# vco_pots.net
KiCad netlist of a schematic drawn in EAGLE
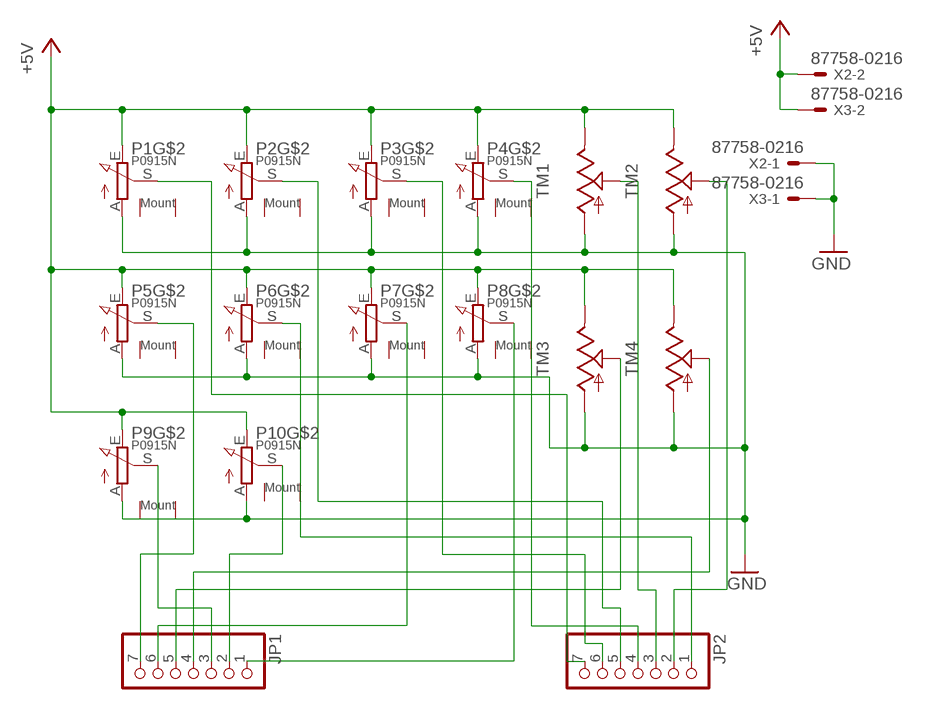
[diagram p0: schematic, sheet 1]

(export (version "E")
  (design (tool "Eeschema 10.0.6"))
  (components
    (comp (ref "JP1")
      (value "PINHD-1X7")
      (footprint "eagle-import:1X07")
      (libsource (lib "eagle-import") (part "PINHD-1X7"))
    )
    (comp (ref "JP2")
      (value "PINHD-1X7")
      (footprint "eagle-import:1X07")
      (libsource (lib "eagle-import") (part "PINHD-1X7"))
    )
    (comp (ref "P1")
      (value "P0915N")
      (footprint "eagle-import:P0915N")
      (libsource (lib "eagle-import") (part "P0915N"))
    )
    (comp (ref "P2")
      (value "P0915N")
      (footprint "eagle-import:P0915N")
      (libsource (lib "eagle-import") (part "P0915N"))
    )
    (comp (ref "P3")
      (value "P0915N")
      (footprint "eagle-import:P0915N")
      (libsource (lib "eagle-import") (part "P0915N"))
    )
    (comp (ref "P4")
      (value "P0915N")
      (footprint "eagle-import:P0915N")
      (libsource (lib "eagle-import") (part "P0915N"))
    )
    (comp (ref "P5")
      (value "P0915N")
      (footprint "eagle-import:P0915N")
      (libsource (lib "eagle-import") (part "P0915N"))
    )
    (comp (ref "P6")
      (value "P0915N")
      (footprint "eagle-import:P0915N")
      (libsource (lib "eagle-import") (part "P0915N"))
    )
    (comp (ref "P7")
      (value "P0915N")
      (footprint "eagle-import:P0915N")
      (libsource (lib "eagle-import") (part "P0915N"))
    )
    (comp (ref "P8")
      (value "P0915N")
      (footprint "eagle-import:P0915N")
      (libsource (lib "eagle-import") (part "P0915N"))
    )
    (comp (ref "P9")
      (value "P0915N")
      (footprint "eagle-import:P0915N")
      (libsource (lib "eagle-import") (part "P0915N"))
    )
    (comp (ref "P10")
      (value "P0915N")
      (footprint "eagle-import:P0915N")
      (libsource (lib "eagle-import") (part "P0915N"))
    )
    (comp (ref "TM1")
      (value "TRIMSLIDE60")
      (footprint "eagle-import:SLIDEPOT-60")
      (libsource (lib "eagle-import") (part "TRIMSLIDE60"))
    )
    (comp (ref "TM2")
      (value "TRIMSLIDE60")
      (footprint "eagle-import:SLIDEPOT-60")
      (libsource (lib "eagle-import") (part "TRIMSLIDE60"))
    )
    (comp (ref "TM3")
      (value "TRIMSLIDE60")
      (footprint "eagle-import:SLIDEPOT-60")
      (libsource (lib "eagle-import") (part "TRIMSLIDE60"))
    )
    (comp (ref "TM4")
      (value "TRIMSLIDE60")
      (footprint "eagle-import:SLIDEPOT-60")
      (libsource (lib "eagle-import") (part "TRIMSLIDE60"))
    )
    (comp (ref "X2")
      (value "87758-0216")
      (footprint "eagle-import:87758-0216")
      (libsource (lib "eagle-import") (part "87758-0216"))
    )
    (comp (ref "X3")
      (value "87758-0216")
      (footprint "eagle-import:87758-0216")
      (libsource (lib "eagle-import") (part "87758-0216"))
    )
  )
  (nets
    (net (code "1") (name "+5V") (class "Default")
      (node (ref "P1") (pin "E") (pinfunction "E_E") (pintype "passive"))
      (node (ref "P10") (pin "E") (pinfunction "E_E") (pintype "passive"))
      (node (ref "P2") (pin "E") (pinfunction "E_E") (pintype "passive"))
      (node (ref "P3") (pin "E") (pinfunction "E_E") (pintype "passive"))
      (node (ref "P4") (pin "E") (pinfunction "E_E") (pintype "passive"))
      (node (ref "P5") (pin "E") (pinfunction "E_E") (pintype "passive"))
      (node (ref "P6") (pin "E") (pinfunction "E_E") (pintype "passive"))
      (node (ref "P7") (pin "E") (pinfunction "E_E") (pintype "passive"))
      (node (ref "P8") (pin "E") (pinfunction "E_E") (pintype "passive"))
      (node (ref "P9") (pin "E") (pinfunction "E_E") (pintype "passive"))
      (node (ref "TM1") (pin "B") (pinfunction "B_B") (pintype "passive"))
      (node (ref "TM2") (pin "B") (pinfunction "B_B") (pintype "passive"))
      (node (ref "TM3") (pin "B") (pinfunction "B_B") (pintype "passive"))
      (node (ref "TM4") (pin "B") (pinfunction "B_B") (pintype "passive"))
      (node (ref "X2") (pin "2") (pinfunction "S_2") (pintype "passive"))
      (node (ref "X3") (pin "2") (pinfunction "S_2") (pintype "passive"))
    )
    (net (code "2") (name "GND") (class "Default")
      (node (ref "P1") (pin "A") (pinfunction "A_A") (pintype "passive"))
      (node (ref "P10") (pin "A") (pinfunction "A_A") (pintype "passive"))
      (node (ref "P2") (pin "A") (pinfunction "A_A") (pintype "passive"))
      (node (ref "P3") (pin "A") (pinfunction "A_A") (pintype "passive"))
      (node (ref "P4") (pin "A") (pinfunction "A_A") (pintype "passive"))
      (node (ref "P5") (pin "A") (pinfunction "A_A") (pintype "passive"))
      (node (ref "P6") (pin "A") (pinfunction "A_A") (pintype "passive"))
      (node (ref "P7") (pin "A") (pinfunction "A_A") (pintype "passive"))
      (node (ref "P8") (pin "A") (pinfunction "A_A") (pintype "passive"))
      (node (ref "P9") (pin "A") (pinfunction "A_A") (pintype "passive"))
      (node (ref "TM1") (pin "A") (pinfunction "A_A") (pintype "passive"))
      (node (ref "TM2") (pin "A") (pinfunction "A_A") (pintype "passive"))
      (node (ref "TM3") (pin "A") (pinfunction "A_A") (pintype "passive"))
      (node (ref "TM4") (pin "A") (pinfunction "A_A") (pintype "passive"))
      (node (ref "X2") (pin "1") (pinfunction "S_1") (pintype "passive"))
      (node (ref "X3") (pin "1") (pinfunction "S_1") (pintype "passive"))
    )
    (net (code "3") (name "Net-(JP1-Pad1)") (class "Default")
      (node (ref "JP1") (pin "1") (pinfunction "1_1") (pintype "passive"))
      (node (ref "P8") (pin "S") (pinfunction "S_S") (pintype "passive"))
    )
    (net (code "4") (name "Net-(JP1-Pad2)") (class "Default")
      (node (ref "JP1") (pin "2") (pinfunction "2_2") (pintype "passive"))
      (node (ref "P10") (pin "S") (pinfunction "S_S") (pintype "passive"))
    )
    (net (code "5") (name "Net-(JP1-Pad3)") (class "Default")
      (node (ref "JP1") (pin "3") (pinfunction "3_3") (pintype "passive"))
      (node (ref "P9") (pin "S") (pinfunction "S_S") (pintype "passive"))
    )
    (net (code "6") (name "Net-(JP1-Pad4)") (class "Default")
      (node (ref "JP1") (pin "4") (pinfunction "4_4") (pintype "passive"))
      (node (ref "TM4") (pin "WIPER") (pinfunction "WIPER_WIPER") (pintype "passive"))
    )
    (net (code "7") (name "Net-(JP1-Pad5)") (class "Default")
      (node (ref "JP1") (pin "5") (pinfunction "5_5") (pintype "passive"))
      (node (ref "TM3") (pin "WIPER") (pinfunction "WIPER_WIPER") (pintype "passive"))
    )
    (net (code "8") (name "Net-(JP1-Pad6)") (class "Default")
      (node (ref "JP1") (pin "6") (pinfunction "6_6") (pintype "passive"))
      (node (ref "P7") (pin "S") (pinfunction "S_S") (pintype "passive"))
    )
    (net (code "9") (name "Net-(JP1-Pad7)") (class "Default")
      (node (ref "JP1") (pin "7") (pinfunction "7_7") (pintype "passive"))
      (node (ref "P5") (pin "S") (pinfunction "S_S") (pintype "passive"))
    )
    (net (code "10") (name "Net-(JP2-Pad1)") (class "Default")
      (node (ref "JP2") (pin "1") (pinfunction "1_1") (pintype "passive"))
      (node (ref "P6") (pin "S") (pinfunction "S_S") (pintype "passive"))
    )
    (net (code "11") (name "Net-(JP2-Pad2)") (class "Default")
      (node (ref "JP2") (pin "2") (pinfunction "2_2") (pintype "passive"))
      (node (ref "TM2") (pin "WIPER") (pinfunction "WIPER_WIPER") (pintype "passive"))
    )
    (net (code "12") (name "Net-(JP2-Pad3)") (class "Default")
      (node (ref "JP2") (pin "3") (pinfunction "3_3") (pintype "passive"))
      (node (ref "TM1") (pin "WIPER") (pinfunction "WIPER_WIPER") (pintype "passive"))
    )
    (net (code "13") (name "Net-(JP2-Pad4)") (class "Default")
      (node (ref "JP2") (pin "4") (pinfunction "4_4") (pintype "passive"))
      (node (ref "P4") (pin "S") (pinfunction "S_S") (pintype "passive"))
    )
    (net (code "14") (name "Net-(JP2-Pad5)") (class "Default")
      (node (ref "JP2") (pin "5") (pinfunction "5_5") (pintype "passive"))
      (node (ref "P2") (pin "S") (pinfunction "S_S") (pintype "passive"))
    )
    (net (code "15") (name "Net-(JP2-Pad6)") (class "Default")
      (node (ref "JP2") (pin "6") (pinfunction "6_6") (pintype "passive"))
      (node (ref "P3") (pin "S") (pinfunction "S_S") (pintype "passive"))
    )
    (net (code "16") (name "Net-(JP2-Pad7)") (class "Default")
      (node (ref "JP2") (pin "7") (pinfunction "7_7") (pintype "passive"))
      (node (ref "P1") (pin "S") (pinfunction "S_S") (pintype "passive"))
    )
    (net (code "17") (name "unconnected-(P1A-GND-PadGND@1)") (class "Default")
      (node (ref "P1") (pin "GND@1") (pinfunction "GND_GND@1") (pintype "passive"))
    )
    (net (code "18") (name "unconnected-(P1A-GND-PadGND@2)") (class "Default")
      (node (ref "P1") (pin "GND@2") (pinfunction "GND_GND@2") (pintype "passive"))
    )
    (net (code "19") (name "unconnected-(P2A-GND-PadGND@1)") (class "Default")
      (node (ref "P2") (pin "GND@1") (pinfunction "GND_GND@1") (pintype "passive"))
    )
    (net (code "20") (name "unconnected-(P2A-GND-PadGND@2)") (class "Default")
      (node (ref "P2") (pin "GND@2") (pinfunction "GND_GND@2") (pintype "passive"))
    )
    (net (code "21") (name "unconnected-(P3A-GND-PadGND@1)") (class "Default")
      (node (ref "P3") (pin "GND@1") (pinfunction "GND_GND@1") (pintype "passive"))
    )
    (net (code "22") (name "unconnected-(P3A-GND-PadGND@2)") (class "Default")
      (node (ref "P3") (pin "GND@2") (pinfunction "GND_GND@2") (pintype "passive"))
    )
    (net (code "23") (name "unconnected-(P4A-GND-PadGND@1)") (class "Default")
      (node (ref "P4") (pin "GND@1") (pinfunction "GND_GND@1") (pintype "passive"))
    )
    (net (code "24") (name "unconnected-(P4A-GND-PadGND@2)") (class "Default")
      (node (ref "P4") (pin "GND@2") (pinfunction "GND_GND@2") (pintype "passive"))
    )
    (net (code "25") (name "unconnected-(P5A-GND-PadGND@1)") (class "Default")
      (node (ref "P5") (pin "GND@1") (pinfunction "GND_GND@1") (pintype "passive"))
    )
    (net (code "26") (name "unconnected-(P5A-GND-PadGND@2)") (class "Default")
      (node (ref "P5") (pin "GND@2") (pinfunction "GND_GND@2") (pintype "passive"))
    )
    (net (code "27") (name "unconnected-(P6A-GND-PadGND@1)") (class "Default")
      (node (ref "P6") (pin "GND@1") (pinfunction "GND_GND@1") (pintype "passive"))
    )
    (net (code "28") (name "unconnected-(P6A-GND-PadGND@2)") (class "Default")
      (node (ref "P6") (pin "GND@2") (pinfunction "GND_GND@2") (pintype "passive"))
    )
    (net (code "29") (name "unconnected-(P7A-GND-PadGND@1)") (class "Default")
      (node (ref "P7") (pin "GND@1") (pinfunction "GND_GND@1") (pintype "passive"))
    )
    (net (code "30") (name "unconnected-(P7A-GND-PadGND@2)") (class "Default")
      (node (ref "P7") (pin "GND@2") (pinfunction "GND_GND@2") (pintype "passive"))
    )
    (net (code "31") (name "unconnected-(P8A-GND-PadGND@1)") (class "Default")
      (node (ref "P8") (pin "GND@1") (pinfunction "GND_GND@1") (pintype "passive"))
    )
    (net (code "32") (name "unconnected-(P8A-GND-PadGND@2)") (class "Default")
      (node (ref "P8") (pin "GND@2") (pinfunction "GND_GND@2") (pintype "passive"))
    )
    (net (code "33") (name "unconnected-(P9A-GND-PadGND@1)") (class "Default")
      (node (ref "P9") (pin "GND@1") (pinfunction "GND_GND@1") (pintype "passive"))
    )
    (net (code "34") (name "unconnected-(P9A-GND-PadGND@2)") (class "Default")
      (node (ref "P9") (pin "GND@2") (pinfunction "GND_GND@2") (pintype "passive"))
    )
    (net (code "35") (name "unconnected-(P10A-GND-PadGND@1)") (class "Default")
      (node (ref "P10") (pin "GND@1") (pinfunction "GND_GND@1") (pintype "passive"))
    )
    (net (code "36") (name "unconnected-(P10A-GND-PadGND@2)") (class "Default")
      (node (ref "P10") (pin "GND@2") (pinfunction "GND_GND@2") (pintype "passive"))
    )
  )
)
